# Sheet1.net
KiCad netlist of a schematic drawn in Altium Designer
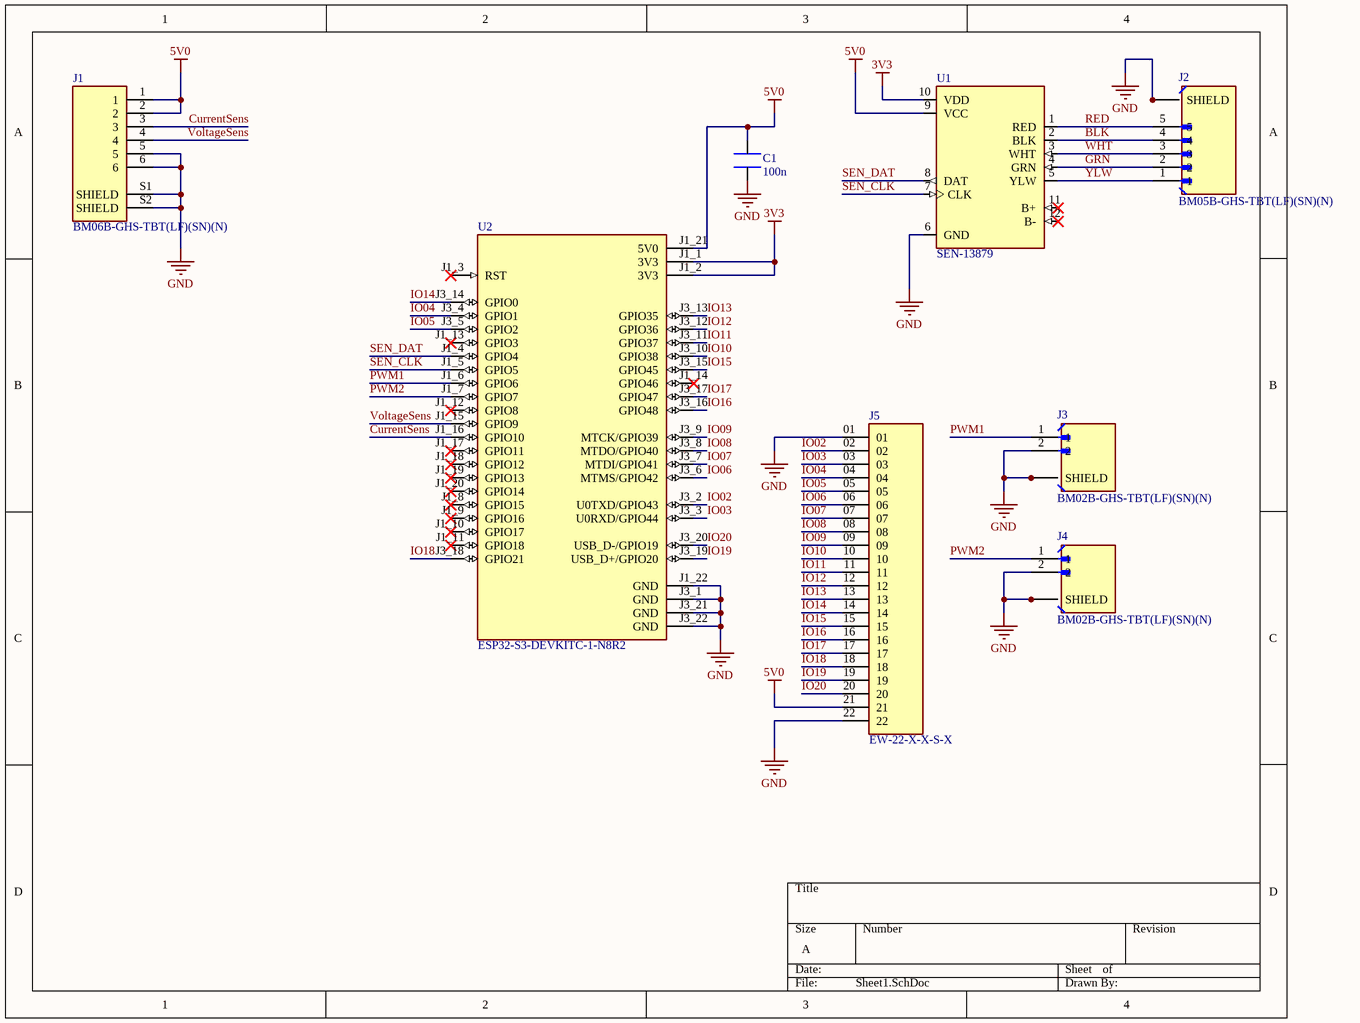
[diagram p0: Sheet1.SchDoc]

(export (version "E")
  (design (tool "Eeschema 10.0.6"))
  (components
    (comp (ref "C1")
      (value "100n")
      (footprint "885382207007:WCAP-CSST_885382207007")
      (fields
        (field (name "MF") "{'manufacturer': u'Wurth Electronics Inc'}")
        (field (name "MP") "885382207007")
      )
      (libsource (lib "*") (part "885382207007"))
    )
    (comp (ref "J1")
      (value "BM06B-GHS-TBT(LF)(SN)(N)")
      (footprint "BM06B-GHS-TBT (LF)(SN)(N):JST_BM06B-GHS-TBT(LF)(SN)(N)")
      (description "Conn Header Gh Top 6pos 1.25mm")
      (fields (field (name "MF") "{'manufacturer': u'JST Corporation'}"))
      (libsource (lib "*") (part "BM06B-GHS-TBT(LF)(SN)(N)"))
    )
    (comp (ref "J2")
      (value "BM05B-GHS-TBT(LF)(SN)(N)")
      (footprint "BM05B-GHS-TBT(LF)(SN)(N):JST_BM05B-GHS-TBT(LF)(SN)(N)")
      (fields (field (name "MF") "{'manufacturer': u'JST Sales'}"))
      (libsource (lib "*") (part "BM05B-GHS-TBT(LF)(SN)(N)"))
    )
    (comp (ref "J3")
      (value "BM02B-GHS-TBT(LF)(SN)(N)")
      (footprint "BM02B-GHS-TBT(LF)(SN)(N):JST_BM02B-GHS-TBT(LF)(SN)(N)")
      (fields (field (name "MF") "{'manufacturer': u'JST Sales'}"))
      (libsource (lib "*") (part "BM02B-GHS-TBT(LF)(SN)(N)"))
    )
    (comp (ref "J4")
      (value "BM02B-GHS-TBT(LF)(SN)(N)")
      (footprint "BM02B-GHS-TBT(LF)(SN)(N):JST_BM02B-GHS-TBT(LF)(SN)(N)")
      (fields (field (name "MF") "{'manufacturer': u'JST Sales'}"))
      (libsource (lib "*") (part "BM02B-GHS-TBT(LF)(SN)(N)"))
    )
    (comp (ref "J5")
      (value "EW-22-X-X-S-X")
      (footprint "EW-22-14-T-S-990:SAMTEC_EW-22-X-X-S-X")
      (fields (field (name "MF") "{'manufacturer': u'Samtec'}"))
      (libsource (lib "*") (part "EW-22-X-X-S-X"))
    )
    (comp (ref "U1")
      (value "SEN-13879")
      (footprint "SEN-13879:SPARKFUN_SEN-13879")
      (description "Load Cell Amp Hx711")
      (fields (field (name "MF") "{'manufacturer': u'SparkFun'}"))
      (libsource (lib "*") (part "SEN-13879"))
    )
    (comp (ref "U2")
      (value "ESP32-S3-DEVKITC-1-N8R2")
      (footprint "ESP32-S3-DEVKITC-1-N8R2:XCVR_ESP32-S3-DEVKITC-1-N8R2")
      (fields (field (name "MF") "{'manufacturer': u'Espressif Systems'}"))
      (libsource (lib "*") (part "ESP32-S3-DEVKITC-1-N8R2"))
    )
  )
  (nets
    (net (code "1") (name "/BLK") (class "Default")
      (node (ref "J2") (pin "4") (pinfunction "4_4") (pintype "passive"))
      (node (ref "U1") (pin "2") (pinfunction "BLK_2") (pintype "bidirectional"))
    )
    (net (code "2") (name "/CurrentSens") (class "Default")
      (node (ref "J1") (pin "3") (pinfunction "3_3") (pintype "passive"))
      (node (ref "U2") (pin "J1_16") (pinfunction "GPIO10_J1_16") (pintype "bidirectional"))
    )
    (net (code "3") (name "/GRN") (class "Default")
      (node (ref "J2") (pin "2") (pinfunction "2_2") (pintype "passive"))
      (node (ref "U1") (pin "4") (pinfunction "GRN_4") (pintype "input"))
    )
    (net (code "4") (name "/IO02") (class "Default")
      (node (ref "J5") (pin "02") (pinfunction "02_02") (pintype "passive"))
      (node (ref "U2") (pin "J3_2") (pinfunction "U0TXD/GPIO43_J3_2") (pintype "bidirectional"))
    )
    (net (code "5") (name "/IO03") (class "Default")
      (node (ref "J5") (pin "03") (pinfunction "03_03") (pintype "passive"))
      (node (ref "U2") (pin "J3_3") (pinfunction "U0RXD/GPIO44_J3_3") (pintype "bidirectional"))
    )
    (net (code "6") (name "/IO04") (class "Default")
      (node (ref "J5") (pin "04") (pinfunction "04_04") (pintype "passive"))
      (node (ref "U2") (pin "J3_4") (pinfunction "GPIO1_J3_4") (pintype "bidirectional"))
    )
    (net (code "7") (name "/IO05") (class "Default")
      (node (ref "J5") (pin "05") (pinfunction "05_05") (pintype "passive"))
      (node (ref "U2") (pin "J3_5") (pinfunction "GPIO2_J3_5") (pintype "bidirectional"))
    )
    (net (code "8") (name "/IO06") (class "Default")
      (node (ref "J5") (pin "06") (pinfunction "06_06") (pintype "passive"))
      (node (ref "U2") (pin "J3_6") (pinfunction "MTMS/GPIO42_J3_6") (pintype "bidirectional"))
    )
    (net (code "9") (name "/IO07") (class "Default")
      (node (ref "J5") (pin "07") (pinfunction "07_07") (pintype "passive"))
      (node (ref "U2") (pin "J3_7") (pinfunction "MTDI/GPIO41_J3_7") (pintype "bidirectional"))
    )
    (net (code "10") (name "/IO08") (class "Default")
      (node (ref "J5") (pin "08") (pinfunction "08_08") (pintype "passive"))
      (node (ref "U2") (pin "J3_8") (pinfunction "MTDO/GPIO40_J3_8") (pintype "bidirectional"))
    )
    (net (code "11") (name "/IO09") (class "Default")
      (node (ref "J5") (pin "09") (pinfunction "09_09") (pintype "passive"))
      (node (ref "U2") (pin "J3_9") (pinfunction "MTCK/GPIO39_J3_9") (pintype "bidirectional"))
    )
    (net (code "12") (name "/IO10") (class "Default")
      (node (ref "J5") (pin "10") (pinfunction "10_10") (pintype "passive"))
      (node (ref "U2") (pin "J3_10") (pinfunction "GPIO38_J3_10") (pintype "bidirectional"))
    )
    (net (code "13") (name "/IO11") (class "Default")
      (node (ref "J5") (pin "11") (pinfunction "11_11") (pintype "passive"))
      (node (ref "U2") (pin "J3_11") (pinfunction "GPIO37_J3_11") (pintype "bidirectional"))
    )
    (net (code "14") (name "/IO12") (class "Default")
      (node (ref "J5") (pin "12") (pinfunction "12_12") (pintype "passive"))
      (node (ref "U2") (pin "J3_12") (pinfunction "GPIO36_J3_12") (pintype "bidirectional"))
    )
    (net (code "15") (name "/IO13") (class "Default")
      (node (ref "J5") (pin "13") (pinfunction "13_13") (pintype "passive"))
      (node (ref "U2") (pin "J3_13") (pinfunction "GPIO35_J3_13") (pintype "bidirectional"))
    )
    (net (code "16") (name "/IO14") (class "Default")
      (node (ref "J5") (pin "14") (pinfunction "14_14") (pintype "passive"))
      (node (ref "U2") (pin "J3_14") (pinfunction "GPIO0_J3_14") (pintype "bidirectional"))
    )
    (net (code "17") (name "/IO15") (class "Default")
      (node (ref "J5") (pin "15") (pinfunction "15_15") (pintype "passive"))
      (node (ref "U2") (pin "J3_15") (pinfunction "GPIO45_J3_15") (pintype "bidirectional"))
    )
    (net (code "18") (name "/IO16") (class "Default")
      (node (ref "J5") (pin "16") (pinfunction "16_16") (pintype "passive"))
      (node (ref "U2") (pin "J3_16") (pinfunction "GPIO48_J3_16") (pintype "bidirectional"))
    )
    (net (code "19") (name "/IO17") (class "Default")
      (node (ref "J5") (pin "17") (pinfunction "17_17") (pintype "passive"))
      (node (ref "U2") (pin "J3_17") (pinfunction "GPIO47_J3_17") (pintype "bidirectional"))
    )
    (net (code "20") (name "/IO18") (class "Default")
      (node (ref "J5") (pin "18") (pinfunction "18_18") (pintype "passive"))
      (node (ref "U2") (pin "J3_18") (pinfunction "GPIO21_J3_18") (pintype "bidirectional"))
    )
    (net (code "21") (name "/IO19") (class "Default")
      (node (ref "J5") (pin "19") (pinfunction "19_19") (pintype "passive"))
      (node (ref "U2") (pin "J3_19") (pinfunction "USB_D+/GPIO20_J3_19") (pintype "bidirectional"))
    )
    (net (code "22") (name "/IO20") (class "Default")
      (node (ref "J5") (pin "20") (pinfunction "20_20") (pintype "passive"))
      (node (ref "U2") (pin "J3_20") (pinfunction "USB_D-/GPIO19_J3_20") (pintype "bidirectional"))
    )
    (net (code "23") (name "/PWM1") (class "Default")
      (node (ref "J3") (pin "1") (pinfunction "1_1") (pintype "passive"))
      (node (ref "U2") (pin "J1_6") (pinfunction "GPIO6_J1_6") (pintype "bidirectional"))
    )
    (net (code "24") (name "/PWM2") (class "Default")
      (node (ref "J4") (pin "1") (pinfunction "1_1") (pintype "passive"))
      (node (ref "U2") (pin "J1_7") (pinfunction "GPIO7_J1_7") (pintype "bidirectional"))
    )
    (net (code "25") (name "/RED") (class "Default")
      (node (ref "J2") (pin "5") (pinfunction "5_5") (pintype "passive"))
      (node (ref "U1") (pin "1") (pinfunction "RED_1") (pintype "bidirectional"))
    )
    (net (code "26") (name "/SEN_CLK") (class "Default")
      (node (ref "U1") (pin "7") (pinfunction "CLK_7") (pintype "input"))
      (node (ref "U2") (pin "J1_5") (pinfunction "GPIO5_J1_5") (pintype "bidirectional"))
    )
    (net (code "27") (name "/SEN_DAT") (class "Default")
      (node (ref "U1") (pin "8") (pinfunction "DAT_8") (pintype "output"))
      (node (ref "U2") (pin "J1_4") (pinfunction "GPIO4_J1_4") (pintype "bidirectional"))
    )
    (net (code "28") (name "/VoltageSens") (class "Default")
      (node (ref "J1") (pin "4") (pinfunction "4_4") (pintype "passive"))
      (node (ref "U2") (pin "J1_15") (pinfunction "GPIO9_J1_15") (pintype "bidirectional"))
    )
    (net (code "29") (name "/WHT") (class "Default")
      (node (ref "J2") (pin "3") (pinfunction "3_3") (pintype "passive"))
      (node (ref "U1") (pin "3") (pinfunction "WHT_3") (pintype "input"))
    )
    (net (code "30") (name "/YLW") (class "Default")
      (node (ref "J2") (pin "1") (pinfunction "1_1") (pintype "passive"))
      (node (ref "U1") (pin "5") (pinfunction "YLW_5") (pintype "bidirectional"))
    )
    (net (code "31") (name "3V3") (class "Default")
      (node (ref "U1") (pin "10") (pinfunction "VDD_10") (pintype "power_in"))
      (node (ref "U2") (pin "J1_1") (pinfunction "3V3_J1_1") (pintype "power_in"))
      (node (ref "U2") (pin "J1_2") (pinfunction "3V3_J1_2") (pintype "power_in"))
    )
    (net (code "32") (name "5V0") (class "Default")
      (node (ref "C1") (pin "2") (pinfunction "2_2") (pintype "passive"))
      (node (ref "J1") (pin "1") (pinfunction "1_1") (pintype "passive"))
      (node (ref "J1") (pin "2") (pinfunction "2_2") (pintype "passive"))
      (node (ref "J5") (pin "21") (pinfunction "21_21") (pintype "passive"))
      (node (ref "U1") (pin "9") (pinfunction "VCC_9") (pintype "power_in"))
      (node (ref "U2") (pin "J1_21") (pinfunction "5V0_J1_21") (pintype "power_in"))
    )
    (net (code "33") (name "GND") (class "Default")
      (node (ref "C1") (pin "1") (pinfunction "1_1") (pintype "passive"))
      (node (ref "J1") (pin "5") (pinfunction "5_5") (pintype "passive"))
      (node (ref "J1") (pin "6") (pinfunction "6_6") (pintype "passive"))
      (node (ref "J1") (pin "S1") (pinfunction "SHIELD_S1") (pintype "passive"))
      (node (ref "J1") (pin "S2") (pinfunction "SHIELD_S2") (pintype "passive"))
      (node (ref "J2") (pin "S1") (pinfunction "SHIELD_S1") (pintype "passive"))
      (node (ref "J2") (pin "S2") (pinfunction "SHIELD_S2") (pintype "passive"))
      (node (ref "J3") (pin "2") (pinfunction "2_2") (pintype "passive"))
      (node (ref "J3") (pin "S1") (pinfunction "SHIELD_S1") (pintype "passive"))
      (node (ref "J3") (pin "S2") (pinfunction "SHIELD_S2") (pintype "passive"))
      (node (ref "J4") (pin "2") (pinfunction "2_2") (pintype "passive"))
      (node (ref "J4") (pin "S1") (pinfunction "SHIELD_S1") (pintype "passive"))
      (node (ref "J4") (pin "S2") (pinfunction "SHIELD_S2") (pintype "passive"))
      (node (ref "J5") (pin "01") (pinfunction "01_01") (pintype "passive"))
      (node (ref "J5") (pin "22") (pinfunction "22_22") (pintype "passive"))
      (node (ref "U1") (pin "6") (pinfunction "GND_6") (pintype "power_in"))
      (node (ref "U2") (pin "J1_22") (pinfunction "GND_J1_22") (pintype "power_in"))
      (node (ref "U2") (pin "J3_1") (pinfunction "GND_J3_1") (pintype "power_in"))
      (node (ref "U2") (pin "J3_21") (pinfunction "GND_J3_21") (pintype "power_in"))
      (node (ref "U2") (pin "J3_22") (pinfunction "GND_J3_22") (pintype "power_in"))
    )
    (net (code "34") (name "unconnected-(U1-B+-Pad11)") (class "Default")
      (node (ref "U1") (pin "11") (pinfunction "B+_11") (pintype "input+no_connect"))
    )
    (net (code "35") (name "unconnected-(U1-B--Pad12)") (class "Default")
      (node (ref "U1") (pin "12") (pinfunction "B-_12") (pintype "input+no_connect"))
    )
    (net (code "36") (name "unconnected-(U2-GPIO3-PadJ1_13)") (class "Default")
      (node (ref "U2") (pin "J1_13") (pinfunction "GPIO3_J1_13") (pintype "bidirectional+no_connect"))
    )
    (net (code "37") (name "unconnected-(U2-GPIO8-PadJ1_12)") (class "Default")
      (node (ref "U2") (pin "J1_12") (pinfunction "GPIO8_J1_12") (pintype "bidirectional+no_connect"))
    )
    (net (code "38") (name "unconnected-(U2-GPIO11-PadJ1_17)") (class "Default")
      (node (ref "U2") (pin "J1_17") (pinfunction "GPIO11_J1_17") (pintype "bidirectional+no_connect"))
    )
    (net (code "39") (name "unconnected-(U2-GPIO12-PadJ1_18)") (class "Default")
      (node (ref "U2") (pin "J1_18") (pinfunction "GPIO12_J1_18") (pintype "bidirectional+no_connect"))
    )
    (net (code "40") (name "unconnected-(U2-GPIO13-PadJ1_19)") (class "Default")
      (node (ref "U2") (pin "J1_19") (pinfunction "GPIO13_J1_19") (pintype "bidirectional+no_connect"))
    )
    (net (code "41") (name "unconnected-(U2-GPIO14-PadJ1_20)") (class "Default")
      (node (ref "U2") (pin "J1_20") (pinfunction "GPIO14_J1_20") (pintype "bidirectional+no_connect"))
    )
    (net (code "42") (name "unconnected-(U2-GPIO15-PadJ1_8)") (class "Default")
      (node (ref "U2") (pin "J1_8") (pinfunction "GPIO15_J1_8") (pintype "bidirectional+no_connect"))
    )
    (net (code "43") (name "unconnected-(U2-GPIO16-PadJ1_9)") (class "Default")
      (node (ref "U2") (pin "J1_9") (pinfunction "GPIO16_J1_9") (pintype "bidirectional+no_connect"))
    )
    (net (code "44") (name "unconnected-(U2-GPIO17-PadJ1_10)") (class "Default")
      (node (ref "U2") (pin "J1_10") (pinfunction "GPIO17_J1_10") (pintype "bidirectional+no_connect"))
    )
    (net (code "45") (name "unconnected-(U2-GPIO18-PadJ1_11)") (class "Default")
      (node (ref "U2") (pin "J1_11") (pinfunction "GPIO18_J1_11") (pintype "bidirectional+no_connect"))
    )
    (net (code "46") (name "unconnected-(U2-GPIO46-PadJ1_14)") (class "Default")
      (node (ref "U2") (pin "J1_14") (pinfunction "GPIO46_J1_14") (pintype "bidirectional+no_connect"))
    )
    (net (code "47") (name "unconnected-(U2-RST-PadJ1_3)") (class "Default")
      (node (ref "U2") (pin "J1_3") (pinfunction "RST_J1_3") (pintype "input+no_connect"))
    )
  )
)
